# SCH___2022-09-24.net
KiCad netlist of a schematic drawn in EasyEDA
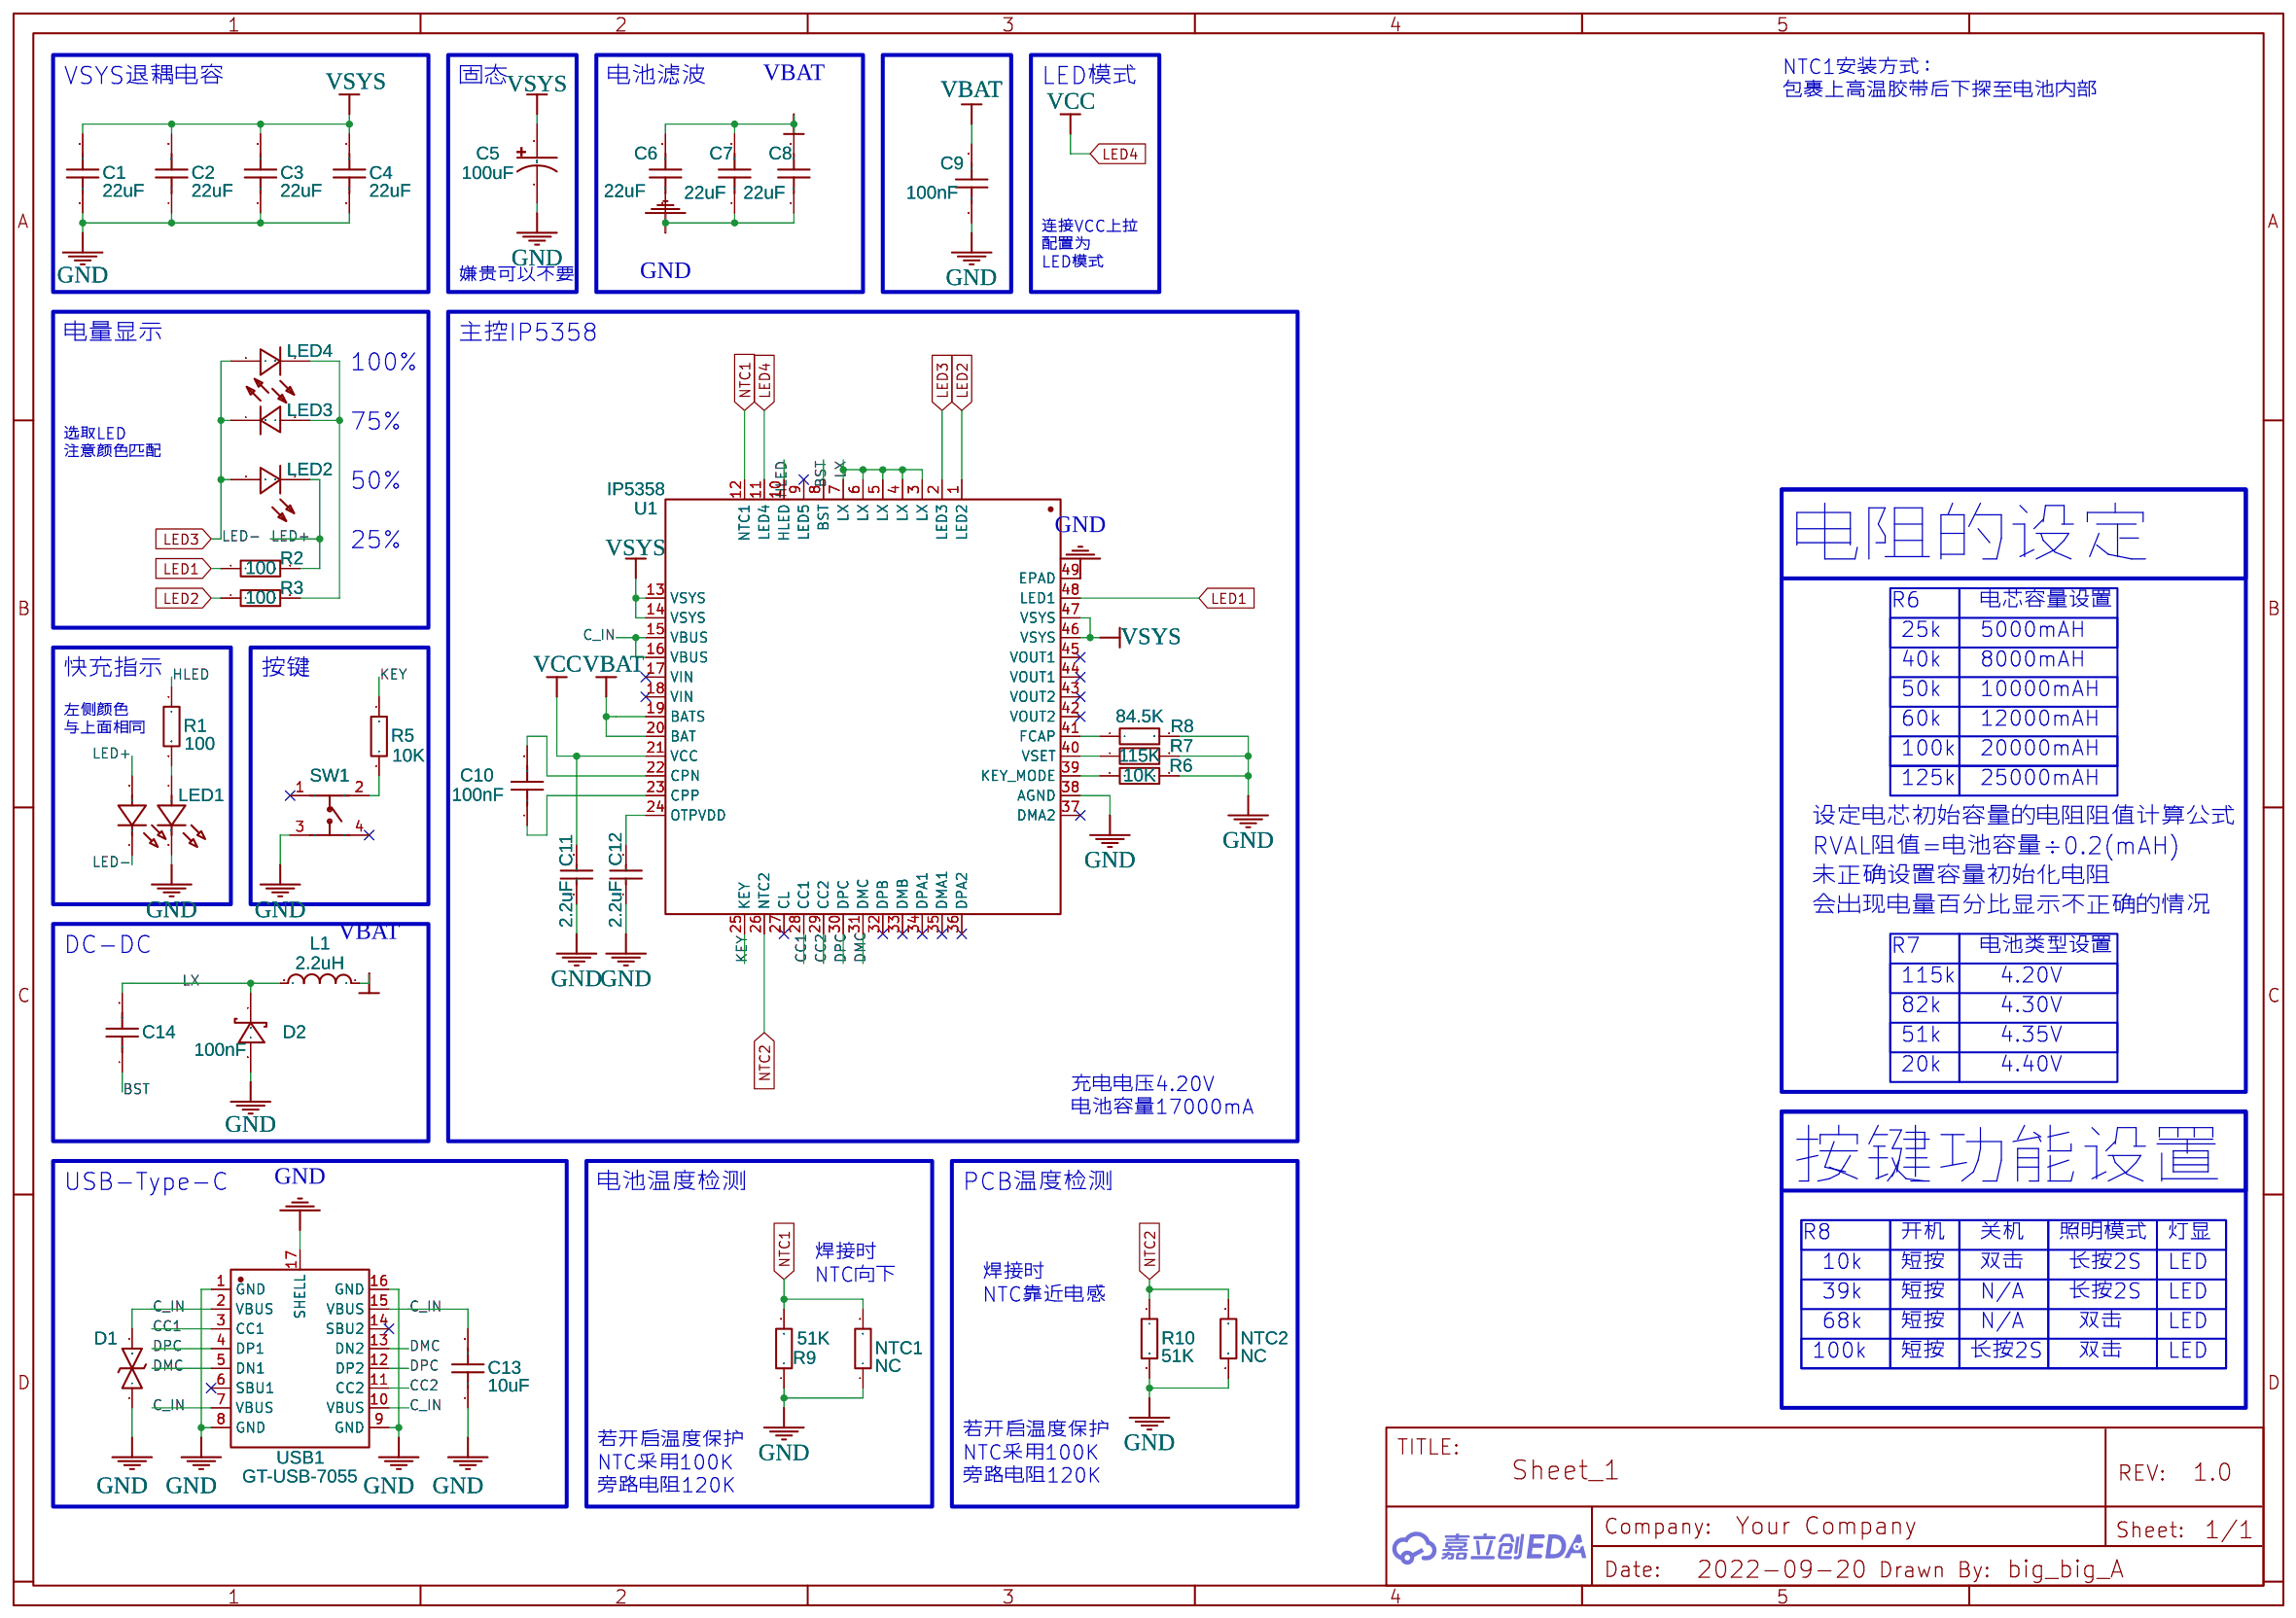
[diagram p0: schematic sheet]

(export (version "E")
  (design (tool "Eeschema 10.0.6"))
  (components
    (comp (ref "C1")
      (value "22uF")
      (fields
        (field (name "BOM_Manufacturer Part") "EMK316ABJ226KL-T")
        (field (name "BOM_Supplier Part") "C319197")
      )
      (libsource (lib "") (part "EMK316ABJ226KL-T"))
    )
    (comp (ref "C2")
      (value "22uF")
      (fields
        (field (name "BOM_Manufacturer Part") "EMK316ABJ226KL-T")
        (field (name "BOM_Supplier Part") "C319197")
      )
      (libsource (lib "") (part "EMK316ABJ226KL-T"))
    )
    (comp (ref "C3")
      (value "22uF")
      (fields
        (field (name "BOM_Manufacturer Part") "EMK316ABJ226KL-T")
        (field (name "BOM_Supplier Part") "C319197")
      )
      (libsource (lib "") (part "EMK316ABJ226KL-T"))
    )
    (comp (ref "C4")
      (value "22uF")
      (fields
        (field (name "BOM_Manufacturer Part") "EMK316ABJ226KL-T")
        (field (name "BOM_Supplier Part") "C319197")
      )
      (libsource (lib "") (part "EMK316ABJ226KL-T_1"))
    )
    (comp (ref "C5")
      (value "100uF")
      (fields
        (field (name "BOM_Manufacturer Part") "SA10JM101A19R55XXX")
        (field (name "BOM_Supplier Part") "C470943")
      )
      (libsource (lib "") (part "SA10JM101A19R55XXX"))
    )
    (comp (ref "C6")
      (value "22uF")
      (fields
        (field (name "BOM_Manufacturer Part") "GRM188R61A226ME15D")
        (field (name "BOM_Supplier Part") "C84419")
      )
      (libsource (lib "") (part "GRM188R61A226ME15D"))
    )
    (comp (ref "C7")
      (value "22uF")
      (fields
        (field (name "BOM_Manufacturer Part") "GRM188R61A226ME15D")
        (field (name "BOM_Supplier Part") "C84419")
      )
      (libsource (lib "") (part "GRM188R61A226ME15D"))
    )
    (comp (ref "C8")
      (value "22uF")
      (fields
        (field (name "BOM_Manufacturer Part") "GRM188R61A226ME15D")
        (field (name "BOM_Supplier Part") "C84419")
      )
      (libsource (lib "") (part "GRM188R61A226ME15D"))
    )
    (comp (ref "C9")
      (value "100nF")
      (fields
        (field (name "BOM_Manufacturer Part") "CL10B104KB8NNNC")
        (field (name "BOM_Supplier Part") "C1591")
      )
      (libsource (lib "") (part "CL10B104KB8NNNC_1"))
    )
    (comp (ref "C10")
      (value "100nF")
      (fields
        (field (name "BOM_Manufacturer Part") "CL10B104KB8NNNC")
        (field (name "BOM_Supplier Part") "C1591")
      )
      (libsource (lib "") (part "CL10B104KB8NNNC"))
    )
    (comp (ref "C11")
      (value "2.2uF")
      (fields
        (field (name "BOM_Manufacturer Part") "CC0603KRX5R7BB225")
        (field (name "BOM_Supplier Part") "C106853")
      )
      (libsource (lib "") (part "CC0603KRX5R7BB225"))
    )
    (comp (ref "C12")
      (value "2.2uF")
      (fields
        (field (name "BOM_Manufacturer Part") "CC0603KRX5R7BB225")
        (field (name "BOM_Supplier Part") "C106853")
      )
      (libsource (lib "") (part "CC0603KRX5R7BB225"))
    )
    (comp (ref "C13")
      (value "10uF")
      (fields
        (field (name "BOM_Manufacturer Part") "GRM188R61E106MA73D")
        (field (name "BOM_Supplier Part") "C91606")
      )
      (libsource (lib "") (part "GRM188R61E106MA73D"))
    )
    (comp (ref "C14")
      (value "100nF")
      (fields
        (field (name "BOM_Manufacturer Part") "CL10B104KB8NNNC")
        (field (name "BOM_Supplier Part") "C1591")
      )
      (libsource (lib "") (part "CL10B104KB8NNNC"))
    )
    (comp (ref "D1")
      (value "SMF18CA_C435488")
      (fields (field (name "BOM_Manufacturer Part") "SMF18CA") (field (name "BOM_Supplier Part") "C435488"))
      (libsource (lib "") (part "SMF18CA_C435488"))
    )
    (comp (ref "D2")
      (value "SS34_C408258")
      (fields (field (name "BOM_Manufacturer Part") "SS34") (field (name "BOM_Supplier Part") "C408258"))
      (libsource (lib "") (part "SS34_C408258"))
    )
    (comp (ref "L1")
      (value "2.2uH")
      (fields
        (field (name "BOM_Manufacturer Part") "SLO0650H2R2MTT")
        (field (name "BOM_Supplier Part") "C216163")
      )
      (libsource (lib "") (part "SLO0624H2R2MTT"))
    )
    (comp (ref "LED1")
      (value "红黄绿双色LED")
      (fields (field (name "BOM_Supplier Part") "C9900023609"))
      (libsource (lib "") (part "红黄绿双色LED"))
    )
    (comp (ref "LED2")
      (value "BL-HGE37A-AV-TRB")
      (fields (field (name "BOM_Supplier Part") "C165979"))
      (libsource (lib "") (part "BL-HGE37A-AV-TRB"))
    )
    (comp (ref "LED3")
      (value "BL-HGE37A-AV-TRB")
      (fields (field (name "BOM_Supplier Part") "C165979"))
      (libsource (lib "") (part "BL-HGE37A-AV-TRB_1"))
    )
    (comp (ref "LED4")
      (value "BL-HGE37A-AV-TRB")
      (fields (field (name "BOM_Supplier Part") "C165979"))
      (libsource (lib "") (part "BL-HGE37A-AV-TRB"))
    )
    (comp (ref "NTC1")
      (value "NC")
      (fields
        (field (name "BOM_Manufacturer Part") "NTC-100K")
        (field (name "BOM_Supplier Part") "C9900024696")
      )
      (libsource (lib "") (part "NTC-100K"))
    )
    (comp (ref "NTC2")
      (value "NC")
      (fields
        (field (name "BOM_Manufacturer Part") "NTC-100K")
        (field (name "BOM_Supplier Part") "C9900024696")
      )
      (libsource (lib "") (part "NTC-100K"))
    )
    (comp (ref "R1")
      (value "100")
      (fields
        (field (name "BOM_Manufacturer Part") "0603WAF1000T5E")
        (field (name "BOM_Supplier Part") "C22775")
      )
      (libsource (lib "") (part "0603WAF1000T5E_1"))
    )
    (comp (ref "R2")
      (value "100")
      (fields
        (field (name "BOM_Manufacturer Part") "0603WAF1000T5E")
        (field (name "BOM_Supplier Part") "C22775")
      )
      (libsource (lib "") (part "0603WAF1000T5E"))
    )
    (comp (ref "R3")
      (value "100")
      (fields
        (field (name "BOM_Manufacturer Part") "0603WAF1000T5E")
        (field (name "BOM_Supplier Part") "C22775")
      )
      (libsource (lib "") (part "0603WAF1000T5E"))
    )
    (comp (ref "R5")
      (value "10K")
      (fields
        (field (name "BOM_Manufacturer Part") "0603WAF1000T5E")
        (field (name "BOM_Supplier Part") "C22775")
      )
      (libsource (lib "") (part "0603WAF1000T5E_1"))
    )
    (comp (ref "R6")
      (value "10K")
      (fields
        (field (name "BOM_Manufacturer Part") "RMCF0603JT10K0")
        (field (name "BOM_Supplier Part") "C238881")
      )
      (libsource (lib "") (part "RMCF0603JT10K0"))
    )
    (comp (ref "R7")
      (value "115K")
      (fields
        (field (name "BOM_Manufacturer Part") "RC0603FR-07115KL")
        (field (name "BOM_Supplier Part") "C137806")
      )
      (libsource (lib "") (part "RC0603FR-07115KL"))
    )
    (comp (ref "R8")
      (value "84.5K")
      (fields
        (field (name "BOM_Manufacturer Part") "RK73H1JTTD5102F")
        (field (name "BOM_Supplier Part") "C160049")
      )
      (libsource (lib "") (part "RK73H1JTTD5102F"))
    )
    (comp (ref "R9")
      (value "51K")
      (fields
        (field (name "BOM_Manufacturer Part") "0603WAF5102T5E")
        (field (name "BOM_Supplier Part") "C23196")
      )
      (libsource (lib "") (part "0603WAF5102T5E"))
    )
    (comp (ref "R10")
      (value "51K")
      (fields
        (field (name "BOM_Manufacturer Part") "0603WAF5102T5E")
        (field (name "BOM_Supplier Part") "C23196")
      )
      (libsource (lib "") (part "0603WAF5102T5E_1"))
    )
    (comp (ref "SW1")
      (value "TC-1150DR-6.0H-160")
      (fields (field (name "BOM_Supplier Part") "C2905090"))
      (libsource (lib "") (part "TC-1150DR-6.0H-160"))
    )
    (comp (ref "U1")
      (value "IP5358")
      (fields (field (name "BOM_Manufacturer Part") "IP5358-BZ") (field (name "BOM_Supplier Part") "C879824"))
      (libsource (lib "") (part "IP5358"))
    )
    (comp (ref "USB1")
      (value "GT-USB-7055")
      (fields (field (name "BOM_Supplier Part") "C2686963"))
      (libsource (lib "") (part "GT-USB-7055"))
    )
  )
  (nets
    (net (code "1") (name "/BST") (class "Default")
      (node (ref "C14") (pin "1") (pinfunction "1_1") (pintype "unspecified"))
      (node (ref "U1") (pin "8") (pinfunction "BST_8") (pintype "unspecified"))
    )
    (net (code "2") (name "/CC1") (class "Default")
      (node (ref "U1") (pin "28") (pinfunction "CC1_28") (pintype "unspecified"))
      (node (ref "USB1") (pin "3") (pinfunction "CC1_3") (pintype "unspecified"))
    )
    (net (code "3") (name "/CC2") (class "Default")
      (node (ref "U1") (pin "29") (pinfunction "CC2_29") (pintype "unspecified"))
      (node (ref "USB1") (pin "11") (pinfunction "CC2_11") (pintype "unspecified"))
    )
    (net (code "4") (name "/C_IN") (class "Default")
      (node (ref "C13") (pin "2") (pinfunction "2_2") (pintype "unspecified"))
      (node (ref "D1") (pin "2") (pinfunction "2_2") (pintype "unspecified"))
      (node (ref "U1") (pin "15") (pinfunction "VBUS_15") (pintype "unspecified"))
      (node (ref "U1") (pin "16") (pinfunction "VBUS_16") (pintype "unspecified"))
      (node (ref "USB1") (pin "10") (pinfunction "VBUS_10") (pintype "unspecified"))
      (node (ref "USB1") (pin "15") (pinfunction "VBUS_15") (pintype "unspecified"))
      (node (ref "USB1") (pin "2") (pinfunction "VBUS_2") (pintype "unspecified"))
      (node (ref "USB1") (pin "7") (pinfunction "VBUS_7") (pintype "unspecified"))
    )
    (net (code "5") (name "/DMC") (class "Default")
      (node (ref "U1") (pin "31") (pinfunction "DMC_31") (pintype "unspecified"))
      (node (ref "USB1") (pin "13") (pinfunction "DN2_13") (pintype "unspecified"))
      (node (ref "USB1") (pin "5") (pinfunction "DN1_5") (pintype "unspecified"))
    )
    (net (code "6") (name "/DPC") (class "Default")
      (node (ref "U1") (pin "30") (pinfunction "DPC_30") (pintype "unspecified"))
      (node (ref "USB1") (pin "12") (pinfunction "DP2_12") (pintype "unspecified"))
      (node (ref "USB1") (pin "4") (pinfunction "DP1_4") (pintype "unspecified"))
    )
    (net (code "7") (name "/HLED") (class "Default")
      (node (ref "R1") (pin "1") (pinfunction "1_1") (pintype "input"))
      (node (ref "U1") (pin "10") (pinfunction "HLED_10") (pintype "unspecified"))
    )
    (net (code "8") (name "/KEY") (class "Default")
      (node (ref "R5") (pin "1") (pinfunction "1_1") (pintype "input"))
      (node (ref "U1") (pin "25") (pinfunction "KEY_25") (pintype "unspecified"))
    )
    (net (code "9") (name "/LED+") (class "Default")
      (node (ref "LED1") (pin "3") (pinfunction "3_3") (pintype "unspecified"))
      (node (ref "LED2") (pin "1") (pinfunction "C_1") (pintype "unspecified"))
      (node (ref "R2") (pin "2") (pinfunction "2_2") (pintype "input"))
    )
    (net (code "10") (name "/LX") (class "Default")
      (node (ref "C14") (pin "2") (pinfunction "2_2") (pintype "unspecified"))
      (node (ref "D2") (pin "1") (pinfunction "C_1") (pintype "unspecified"))
      (node (ref "L1") (pin "1") (pinfunction "1_1") (pintype "unspecified"))
      (node (ref "U1") (pin "3") (pinfunction "LX_3") (pintype "unspecified"))
      (node (ref "U1") (pin "4") (pinfunction "LX_4") (pintype "unspecified"))
      (node (ref "U1") (pin "5") (pinfunction "LX_5") (pintype "unspecified"))
      (node (ref "U1") (pin "6") (pinfunction "LX_6") (pintype "unspecified"))
      (node (ref "U1") (pin "7") (pinfunction "LX_7") (pintype "unspecified"))
    )
    (net (code "11") (name "GND") (class "Default")
      (node (ref "C1") (pin "1") (pinfunction "1_1") (pintype "unspecified"))
      (node (ref "C11") (pin "1") (pinfunction "1_1") (pintype "input"))
      (node (ref "C12") (pin "1") (pinfunction "1_1") (pintype "input"))
      (node (ref "C13") (pin "1") (pinfunction "1_1") (pintype "unspecified"))
      (node (ref "C2") (pin "1") (pinfunction "1_1") (pintype "unspecified"))
      (node (ref "C3") (pin "1") (pinfunction "1_1") (pintype "unspecified"))
      (node (ref "C4") (pin "2") (pinfunction "2_2") (pintype "unspecified"))
      (node (ref "C5") (pin "2") (pinfunction "2_2") (pintype "unspecified"))
      (node (ref "C6") (pin "1") (pinfunction "1_1") (pintype "unspecified"))
      (node (ref "C7") (pin "1") (pinfunction "1_1") (pintype "unspecified"))
      (node (ref "C8") (pin "1") (pinfunction "1_1") (pintype "unspecified"))
      (node (ref "C9") (pin "2") (pinfunction "2_2") (pintype "unspecified"))
      (node (ref "D1") (pin "1") (pinfunction "1_1") (pintype "unspecified"))
      (node (ref "D2") (pin "2") (pinfunction "A_2") (pintype "unspecified"))
      (node (ref "LED1") (pin "2") (pinfunction "2_2") (pintype "unspecified"))
      (node (ref "NTC1") (pin "1") (pinfunction "1_1") (pintype "unspecified"))
      (node (ref "NTC2") (pin "1") (pinfunction "1_1") (pintype "unspecified"))
      (node (ref "R10") (pin "2") (pinfunction "2_2") (pintype "input"))
      (node (ref "R6") (pin "1") (pinfunction "1_1") (pintype "unspecified"))
      (node (ref "R7") (pin "2") (pinfunction "2_2") (pintype "input"))
      (node (ref "R8") (pin "2") (pinfunction "2_2") (pintype "unspecified"))
      (node (ref "R9") (pin "1") (pinfunction "1_1") (pintype "input"))
      (node (ref "SW1") (pin "3") (pinfunction "3_3") (pintype "unspecified"))
      (node (ref "U1") (pin "38") (pinfunction "AGND_38") (pintype "unspecified"))
      (node (ref "U1") (pin "49") (pinfunction "EPAD_49") (pintype "unspecified"))
      (node (ref "USB1") (pin "1") (pinfunction "GND_1") (pintype "unspecified"))
      (node (ref "USB1") (pin "16") (pinfunction "GND_16") (pintype "unspecified"))
      (node (ref "USB1") (pin "17") (pinfunction "SHELL_17") (pintype "unspecified"))
      (node (ref "USB1") (pin "8") (pinfunction "GND_8") (pintype "unspecified"))
      (node (ref "USB1") (pin "9") (pinfunction "GND_9") (pintype "unspecified"))
    )
    (net (code "12") (name "LED1") (class "Default")
      (node (ref "R2") (pin "1") (pinfunction "1_1") (pintype "input"))
      (node (ref "U1") (pin "48") (pinfunction "LED1_48") (pintype "unspecified"))
    )
    (net (code "13") (name "LED2") (class "Default")
      (node (ref "R3") (pin "1") (pinfunction "1_1") (pintype "input"))
      (node (ref "U1") (pin "1") (pinfunction "LED2_1") (pintype "unspecified"))
    )
    (net (code "14") (name "LED3") (class "Default")
      (node (ref "LED1") (pin "4") (pinfunction "4_4") (pintype "unspecified"))
      (node (ref "LED2") (pin "2") (pinfunction "A_2") (pintype "unspecified"))
      (node (ref "LED3") (pin "1") (pinfunction "C_1") (pintype "unspecified"))
      (node (ref "LED4") (pin "2") (pinfunction "A_2") (pintype "unspecified"))
      (node (ref "U1") (pin "2") (pinfunction "LED3_2") (pintype "unspecified"))
    )
    (net (code "15") (name "LED4") (class "Default")
      (node (ref "C11") (pin "2") (pinfunction "2_2") (pintype "input"))
      (node (ref "U1") (pin "11") (pinfunction "LED4_11") (pintype "unspecified"))
      (node (ref "U1") (pin "21") (pinfunction "VCC_21") (pintype "unspecified"))
    )
    (net (code "16") (name "NTC1") (class "Default")
      (node (ref "NTC1") (pin "2") (pinfunction "2_2") (pintype "unspecified"))
      (node (ref "R9") (pin "2") (pinfunction "2_2") (pintype "input"))
      (node (ref "U1") (pin "12") (pinfunction "NTC1_12") (pintype "unspecified"))
    )
    (net (code "17") (name "NTC2") (class "Default")
      (node (ref "NTC2") (pin "2") (pinfunction "2_2") (pintype "unspecified"))
      (node (ref "R10") (pin "1") (pinfunction "1_1") (pintype "input"))
      (node (ref "U1") (pin "26") (pinfunction "NTC2_26") (pintype "unspecified"))
    )
    (net (code "18") (name "Net-(LED1-Pad1)") (class "Default")
      (node (ref "LED1") (pin "1") (pinfunction "1_1") (pintype "unspecified"))
      (node (ref "R1") (pin "2") (pinfunction "2_2") (pintype "input"))
    )
    (net (code "19") (name "Net-(LED3-A)") (class "Default")
      (node (ref "LED3") (pin "2") (pinfunction "A_2") (pintype "unspecified"))
      (node (ref "LED4") (pin "1") (pinfunction "C_1") (pintype "unspecified"))
      (node (ref "R3") (pin "2") (pinfunction "2_2") (pintype "input"))
    )
    (net (code "20") (name "Net-(R5-Pad2)") (class "Default")
      (node (ref "R5") (pin "2") (pinfunction "2_2") (pintype "input"))
      (node (ref "SW1") (pin "2") (pinfunction "2_2") (pintype "unspecified"))
    )
    (net (code "21") (name "Net-(U1-CPN)") (class "Default")
      (node (ref "C10") (pin "2") (pinfunction "2_2") (pintype "unspecified"))
      (node (ref "U1") (pin "22") (pinfunction "CPN_22") (pintype "unspecified"))
    )
    (net (code "22") (name "Net-(U1-CPP)") (class "Default")
      (node (ref "C10") (pin "1") (pinfunction "1_1") (pintype "unspecified"))
      (node (ref "U1") (pin "23") (pinfunction "CPP_23") (pintype "unspecified"))
    )
    (net (code "23") (name "Net-(U1-FCAP)") (class "Default")
      (node (ref "R8") (pin "1") (pinfunction "1_1") (pintype "unspecified"))
      (node (ref "U1") (pin "41") (pinfunction "FCAP_41") (pintype "unspecified"))
    )
    (net (code "24") (name "Net-(U1-KEY_MODE)") (class "Default")
      (node (ref "R6") (pin "2") (pinfunction "2_2") (pintype "unspecified"))
      (node (ref "U1") (pin "39") (pinfunction "KEY_MODE_39") (pintype "unspecified"))
    )
    (net (code "25") (name "Net-(U1-OTPVDD)") (class "Default")
      (node (ref "C12") (pin "2") (pinfunction "2_2") (pintype "input"))
      (node (ref "U1") (pin "24") (pinfunction "OTPVDD_24") (pintype "unspecified"))
    )
    (net (code "26") (name "Net-(U1-VSET)") (class "Default")
      (node (ref "R7") (pin "1") (pinfunction "1_1") (pintype "input"))
      (node (ref "U1") (pin "40") (pinfunction "VSET_40") (pintype "unspecified"))
    )
    (net (code "27") (name "VBAT") (class "Default")
      (node (ref "C6") (pin "2") (pinfunction "2_2") (pintype "unspecified"))
      (node (ref "C7") (pin "2") (pinfunction "2_2") (pintype "unspecified"))
      (node (ref "C8") (pin "2") (pinfunction "2_2") (pintype "unspecified"))
      (node (ref "C9") (pin "1") (pinfunction "1_1") (pintype "unspecified"))
      (node (ref "L1") (pin "2") (pinfunction "2_2") (pintype "unspecified"))
      (node (ref "U1") (pin "19") (pinfunction "BATS_19") (pintype "unspecified"))
      (node (ref "U1") (pin "20") (pinfunction "BAT_20") (pintype "unspecified"))
    )
    (net (code "28") (name "VSYS") (class "Default")
      (node (ref "C1") (pin "2") (pinfunction "2_2") (pintype "unspecified"))
      (node (ref "C2") (pin "2") (pinfunction "2_2") (pintype "unspecified"))
      (node (ref "C3") (pin "2") (pinfunction "2_2") (pintype "unspecified"))
      (node (ref "C4") (pin "1") (pinfunction "1_1") (pintype "unspecified"))
      (node (ref "C5") (pin "1") (pinfunction "1_1") (pintype "unspecified"))
      (node (ref "U1") (pin "13") (pinfunction "VSYS_13") (pintype "unspecified"))
      (node (ref "U1") (pin "14") (pinfunction "VSYS_14") (pintype "unspecified"))
      (node (ref "U1") (pin "46") (pinfunction "VSYS_46") (pintype "unspecified"))
      (node (ref "U1") (pin "47") (pinfunction "VSYS_47") (pintype "unspecified"))
    )
    (net (code "29") (name "unconnected-(SW1-Pad1)") (class "Default")
      (node (ref "SW1") (pin "1") (pinfunction "1_1") (pintype "unspecified+no_connect"))
    )
    (net (code "30") (name "unconnected-(SW1-Pad4)") (class "Default")
      (node (ref "SW1") (pin "4") (pinfunction "4_4") (pintype "unspecified+no_connect"))
    )
    (net (code "31") (name "unconnected-(U1-CL-Pad27)") (class "Default")
      (node (ref "U1") (pin "27") (pinfunction "CL_27") (pintype "unspecified+no_connect"))
    )
    (net (code "32") (name "unconnected-(U1-DMA1-Pad35)") (class "Default")
      (node (ref "U1") (pin "35") (pinfunction "DMA1_35") (pintype "unspecified+no_connect"))
    )
    (net (code "33") (name "unconnected-(U1-DMA2-Pad37)") (class "Default")
      (node (ref "U1") (pin "37") (pinfunction "DMA2_37") (pintype "unspecified+no_connect"))
    )
    (net (code "34") (name "unconnected-(U1-DMB-Pad33)") (class "Default")
      (node (ref "U1") (pin "33") (pinfunction "DMB_33") (pintype "unspecified+no_connect"))
    )
    (net (code "35") (name "unconnected-(U1-DPA1-Pad34)") (class "Default")
      (node (ref "U1") (pin "34") (pinfunction "DPA1_34") (pintype "unspecified+no_connect"))
    )
    (net (code "36") (name "unconnected-(U1-DPA2-Pad36)") (class "Default")
      (node (ref "U1") (pin "36") (pinfunction "DPA2_36") (pintype "unspecified+no_connect"))
    )
    (net (code "37") (name "unconnected-(U1-DPB-Pad32)") (class "Default")
      (node (ref "U1") (pin "32") (pinfunction "DPB_32") (pintype "unspecified+no_connect"))
    )
    (net (code "38") (name "unconnected-(U1-LED5-Pad9)") (class "Default")
      (node (ref "U1") (pin "9") (pinfunction "LED5_9") (pintype "unspecified+no_connect"))
    )
    (net (code "39") (name "unconnected-(U1-VIN-Pad17)") (class "Default")
      (node (ref "U1") (pin "17") (pinfunction "VIN_17") (pintype "unspecified+no_connect"))
    )
    (net (code "40") (name "unconnected-(U1-VIN-Pad18)") (class "Default")
      (node (ref "U1") (pin "18") (pinfunction "VIN_18") (pintype "unspecified+no_connect"))
    )
    (net (code "41") (name "unconnected-(U1-VOUT1-Pad44)") (class "Default")
      (node (ref "U1") (pin "44") (pinfunction "VOUT1_44") (pintype "unspecified+no_connect"))
    )
    (net (code "42") (name "unconnected-(U1-VOUT1-Pad45)") (class "Default")
      (node (ref "U1") (pin "45") (pinfunction "VOUT1_45") (pintype "unspecified+no_connect"))
    )
    (net (code "43") (name "unconnected-(U1-VOUT2-Pad42)") (class "Default")
      (node (ref "U1") (pin "42") (pinfunction "VOUT2_42") (pintype "unspecified+no_connect"))
    )
    (net (code "44") (name "unconnected-(U1-VOUT2-Pad43)") (class "Default")
      (node (ref "U1") (pin "43") (pinfunction "VOUT2_43") (pintype "unspecified+no_connect"))
    )
    (net (code "45") (name "unconnected-(USB1-SBU1-Pad6)") (class "Default")
      (node (ref "USB1") (pin "6") (pinfunction "SBU1_6") (pintype "unspecified+no_connect"))
    )
    (net (code "46") (name "unconnected-(USB1-SBU2-Pad14)") (class "Default")
      (node (ref "USB1") (pin "14") (pinfunction "SBU2_14") (pintype "unspecified+no_connect"))
    )
  )
)
